# Sen_PF.net
KiCad netlist of a schematic drawn in Altium Designer
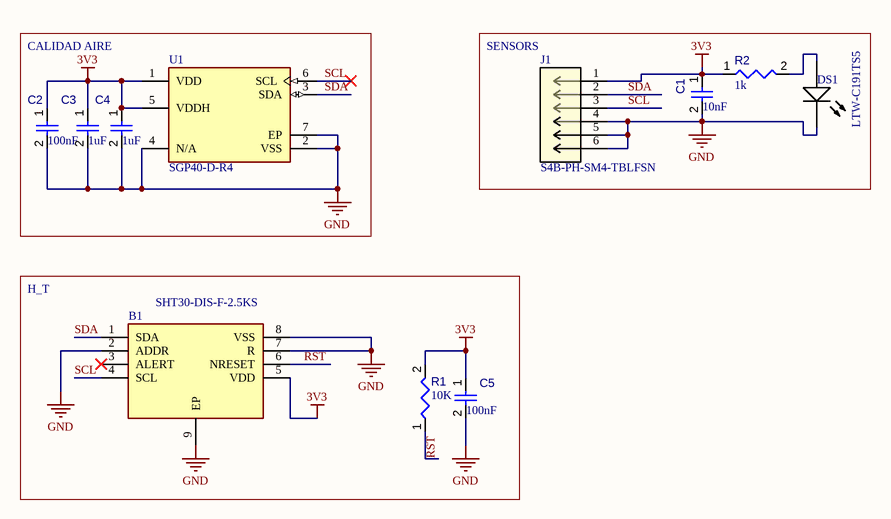
[diagram p0: Sen_PF.SchDoc]

(export (version "E")
  (design (tool "Eeschema 10.0.6"))
  (components
    (comp (ref "B1")
      (value "SHT30-DIS-F-2.5KS")
      (footprint "SON50P250X250X100-9N-D")
      (description "Humidity and Temperature Sensor")
      (libsource (lib "SHT30-DIS-F-2.5KS") (part "SHT30-DIS-F-2.5KS"))
    )
    (comp (ref "C1")
      (value "10nF")
      (footprint "CAPC1608X90X40ML10T20")
      (description "Chip Capacitor, 100 nF, +/- 10%, 50 V, 0603 (1608 Metric)")
      (fields (field (name "TOLERANCE") "10%") (field (name "Comment") "Capacitor 100 nF +/-10% 50 V 0603"))
      (libsource (lib "UdeA") (part "CAP-NP-2"))
    )
    (comp (ref "C2")
      (value "100nF")
      (footprint "CAPC1608X90X40NL10T20")
      (description "Chip Capacitor, 100 nF, +/- 10%, 50 V, 0603 (1608 Metric)")
      (fields (field (name "TOLERANCE") "10%") (field (name "Comment") "Capacitor 100 nF +/-10% 50 V 0603"))
      (libsource (lib "UdeA") (part "CAP-NP-2"))
    )
    (comp (ref "C3")
      (value "1uF")
      (footprint "CAPC1608X90X40NL10T20")
      (description "Chip Capacitor, 100 nF, +/- 10%, 50 V, 0603 (1608 Metric)")
      (fields (field (name "TOLERANCE") "10%") (field (name "Comment") "Capacitor 100 nF +/-10% 50 V 0603"))
      (libsource (lib "UdeA") (part "CAP-NP-2"))
    )
    (comp (ref "C4")
      (value "1uF")
      (footprint "CAPC1608X90X40NL10T20")
      (description "Chip Capacitor, 100 nF, +/- 10%, 50 V, 0603 (1608 Metric)")
      (fields (field (name "TOLERANCE") "10%") (field (name "Comment") "Capacitor 100 nF +/-10% 50 V 0603"))
      (libsource (lib "UdeA") (part "CAP-NP-2"))
    )
    (comp (ref "C5")
      (value "100nF")
      (footprint "CAPC1608X90X40NL10T20")
      (description "Chip Capacitor, 100 nF, +/- 10%, 50 V, 0603 (1608 Metric)")
      (fields (field (name "TOLERANCE") "10%") (field (name "Comment") "Capacitor 100 nF +/-10% 50 V 0603"))
      (libsource (lib "UdeA") (part "CAP-NP-2"))
    )
    (comp (ref "DS1")
      (value "LTW-C191TS5")
      (footprint "LTST-LTW-C191TS5_V")
      (description "LED Uni-Color White, 70 mW, 20 mA, -20 to 80 degC, 2-Pin SMD, RoHS, Tape and Reel")
      (fields (field (name "POWER") "70mW") (field (name "MANUFACTURER") "Lite-On"))
      (libsource (lib "UdeA") (part "LED-WHITE-AK-2"))
    )
    (comp (ref "J1")
      (value "S4B-PH-SM4-TBLFSN")
      (footprint "CONN_S4B-PH-SM4-TBLFSN_JST")
      (description "No Description Available")
      (libsource (lib "S4B-PH-SM4-TBLFSN") (part "S4B-PH-SM4-TBLFSN"))
    )
    (comp (ref "R1")
      (value "10K")
      (footprint "RESC1608X55X25ML10T15")
      (description "Chip Resistor, 10 KOhm, +/- 1%, 01 W, -55 to 155 degC, 0603 (1608 Metric)")
      (fields (field (name "POWER") "100mW") (field (name "TOLERANCE") "1%"))
      (libsource (lib "UdeA") (part "RES-2"))
    )
    (comp (ref "R2")
      (value "1k")
      (footprint "RESC1608X55X25ML10T15")
      (description "Chip Resistor, 10 KOhm, +/- 1%, 01 W, -55 to 155 degC, 0603 (1608 Metric)")
      (fields (field (name "POWER") "100mW") (field (name "TOLERANCE") "1%"))
      (libsource (lib "UdeA") (part "RES-2"))
    )
    (comp (ref "U1")
      (value "SGP40-D-R4")
      (footprint "FP-SGP40-D-R4-MFG")
      (description "AIR QUALITY GAS SENSOR FOR VOC'S")
      (libsource (lib "Altium Content Vault") (part "7bf7b638bf8e6ffe2d764ddf3150cd1"))
    )
  )
  (nets
    (net (code "1") (name "/RST") (class "Default")
      (node (ref "B1") (pin "6") (pinfunction "NRESET_6") (pintype "passive"))
      (node (ref "R1") (pin "1") (pinfunction "1_1") (pintype "passive"))
    )
    (net (code "2") (name "/SCL") (class "Default")
      (node (ref "B1") (pin "4") (pinfunction "SCL_4") (pintype "passive"))
      (node (ref "J1") (pin "3") (pinfunction "3_3") (pintype "passive"))
      (node (ref "U1") (pin "6") (pinfunction "SCL_6") (pintype "input"))
    )
    (net (code "3") (name "/SDA") (class "Default")
      (node (ref "B1") (pin "1") (pinfunction "SDA_1") (pintype "passive"))
      (node (ref "J1") (pin "2") (pinfunction "2_2") (pintype "passive"))
      (node (ref "U1") (pin "3") (pinfunction "SDA_3") (pintype "bidirectional"))
    )
    (net (code "4") (name "3V3") (class "Default")
      (node (ref "B1") (pin "5") (pinfunction "VDD_5") (pintype "passive"))
      (node (ref "C1") (pin "1") (pinfunction "1_1") (pintype "passive"))
      (node (ref "C2") (pin "1") (pinfunction "1_1") (pintype "passive"))
      (node (ref "C3") (pin "1") (pinfunction "1_1") (pintype "passive"))
      (node (ref "C4") (pin "1") (pinfunction "1_1") (pintype "passive"))
      (node (ref "C5") (pin "1") (pinfunction "1_1") (pintype "passive"))
      (node (ref "J1") (pin "1") (pinfunction "1_1") (pintype "passive"))
      (node (ref "R1") (pin "2") (pinfunction "2_2") (pintype "passive"))
      (node (ref "R2") (pin "1") (pinfunction "1_1") (pintype "passive"))
      (node (ref "U1") (pin "1") (pinfunction "VDD_1") (pintype "power_in"))
      (node (ref "U1") (pin "5") (pinfunction "VDDH_5") (pintype "power_in"))
    )
    (net (code "5") (name "GND") (class "Default")
      (node (ref "B1") (pin "2") (pinfunction "ADDR_2") (pintype "passive"))
      (node (ref "B1") (pin "7") (pinfunction "R_7") (pintype "passive"))
      (node (ref "B1") (pin "8") (pinfunction "VSS_8") (pintype "passive"))
      (node (ref "B1") (pin "9") (pinfunction "EP_9") (pintype "passive"))
      (node (ref "C1") (pin "2") (pinfunction "2_2") (pintype "passive"))
      (node (ref "C2") (pin "2") (pinfunction "2_2") (pintype "passive"))
      (node (ref "C3") (pin "2") (pinfunction "2_2") (pintype "passive"))
      (node (ref "C4") (pin "2") (pinfunction "2_2") (pintype "passive"))
      (node (ref "C5") (pin "2") (pinfunction "2_2") (pintype "passive"))
      (node (ref "DS1") (pin "2") (pinfunction "K_2") (pintype "passive"))
      (node (ref "J1") (pin "4") (pinfunction "4_4") (pintype "passive"))
      (node (ref "J1") (pin "5") (pinfunction "5_5") (pintype "passive"))
      (node (ref "J1") (pin "6") (pinfunction "6_6") (pintype "passive"))
      (node (ref "U1") (pin "2") (pinfunction "VSS_2") (pintype "power_in"))
      (node (ref "U1") (pin "4") (pinfunction "N/A_4") (pintype "passive"))
      (node (ref "U1") (pin "7") (pinfunction "EP_7") (pintype "passive"))
    )
    (net (code "6") (name "Net-(DS1-A)") (class "Default")
      (node (ref "DS1") (pin "1") (pinfunction "A_1") (pintype "passive"))
      (node (ref "R2") (pin "2") (pinfunction "2_2") (pintype "passive"))
    )
    (net (code "7") (name "unconnected-(B1-ALERT-Pad3)") (class "Default")
      (node (ref "B1") (pin "3") (pinfunction "ALERT_3") (pintype "passive+no_connect"))
    )
  )
)
